# electronicProject.net
KiCad netlist of a schematic drawn in EAGLE
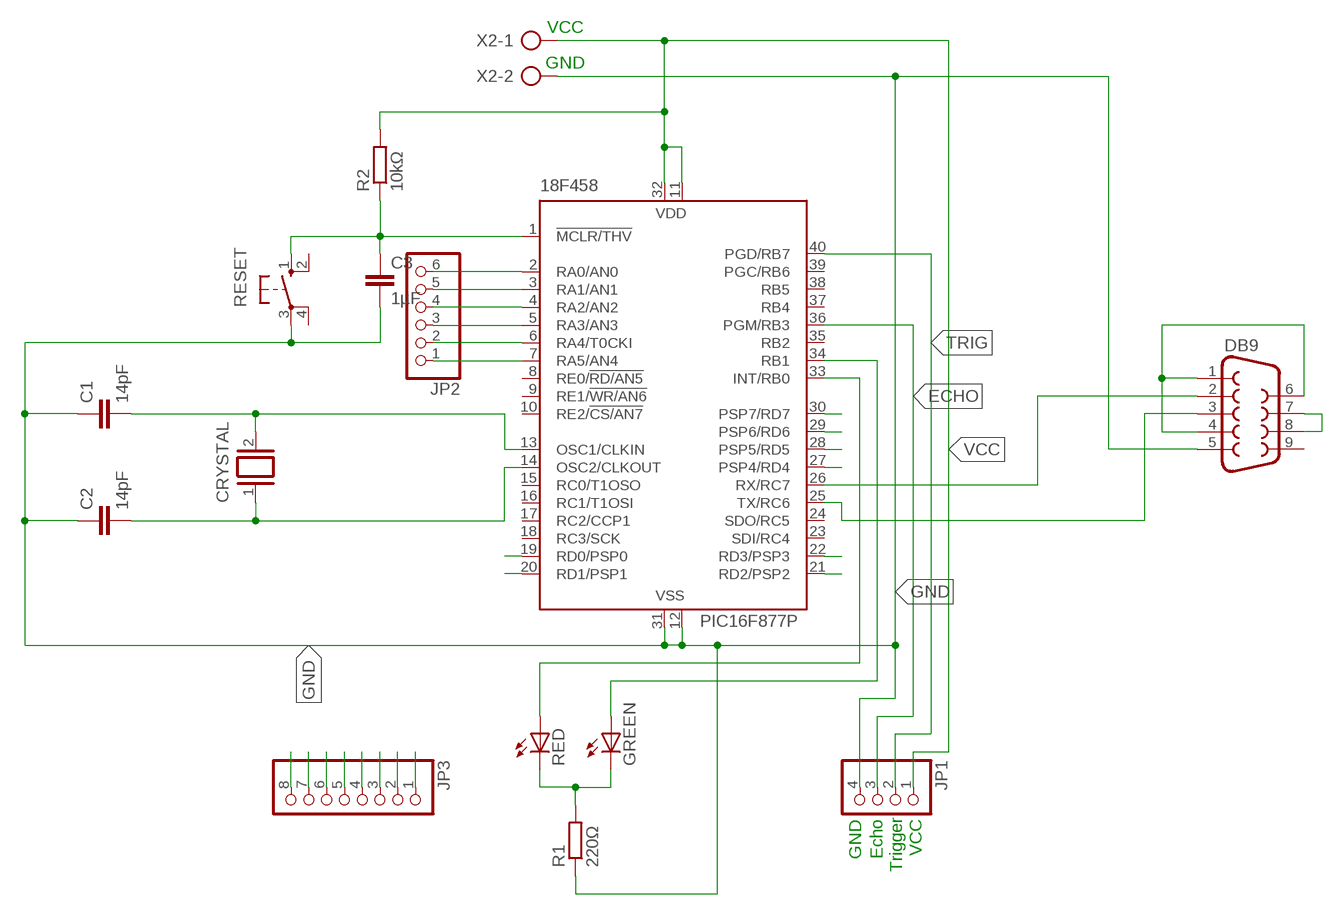
[diagram p0: schematic, sheet 1]

(export (version "E")
  (design (tool "Eeschema 10.0.6"))
  (components
    (comp (ref "18F458")
      (value "PIC16F877P")
      (footprint "eagle-import:DIL40")
      (fields (field (name "MF") "MICROCHIP") (field (name "MPN") "PIC16F877-04/P"))
      (libsource (lib "eagle-import") (part "PIC16F87P7"))
    )
    (comp (ref "C1")
      (value "14pF")
      (footprint "eagle-import:C025-024X044")
      (libsource (lib "eagle-import") (part "C-EU025-024X044"))
    )
    (comp (ref "C2")
      (value "14pF")
      (footprint "eagle-import:C025-024X044")
      (libsource (lib "eagle-import") (part "C-EU025-024X044"))
    )
    (comp (ref "C3")
      (value "1µF")
      (footprint "eagle-import:C025-024X044")
      (libsource (lib "eagle-import") (part "C-EU025-024X044"))
    )
    (comp (ref "CRYSTAL")
      (value "XTAL/S")
      (footprint "eagle-import:QS")
      (libsource (lib "eagle-import") (part "XTAL/S"))
    )
    (comp (ref "DB9")
      (value "F09H")
      (footprint "eagle-import:F09H")
      (libsource (lib "eagle-import") (part "F09H"))
    )
    (comp (ref "GREEN")
      (value "LED3MM")
      (footprint "eagle-import:LED3MM")
      (libsource (lib "eagle-import") (part "LED3MM"))
    )
    (comp (ref "JP1")
      (value "PINHD-1X4")
      (footprint "eagle-import:1X04")
      (libsource (lib "eagle-import") (part "PINHD-1X4"))
    )
    (comp (ref "JP2")
      (value "PINHD-1X6")
      (footprint "eagle-import:1X06")
      (libsource (lib "eagle-import") (part "PINHD-1X6"))
    )
    (comp (ref "JP3")
      (value "PINHD-1X8")
      (footprint "eagle-import:1X08")
      (libsource (lib "eagle-import") (part "PINHD-1X8"))
    )
    (comp (ref "R1")
      (value "220Ω")
      (footprint "eagle-import:0207_10")
      (libsource (lib "eagle-import") (part "R-EU_0207/10"))
    )
    (comp (ref "R2")
      (value "10kΩ")
      (footprint "eagle-import:0207_10")
      (libsource (lib "eagle-import") (part "R-EU_0207/10"))
    )
    (comp (ref "RED")
      (value "LED3MM")
      (footprint "eagle-import:LED3MM")
      (libsource (lib "eagle-import") (part "LED3MM"))
    )
    (comp (ref "RESET")
      (value "10-XX")
      (footprint "eagle-import:B3F-10XX")
      (fields (field (name "MPN") "B3F-1000"))
      (libsource (lib "eagle-import") (part "10-XX"))
    )
    (comp (ref "X2")
      (value "AK300/2")
      (footprint "eagle-import:AK300_2")
      (libsource (lib "eagle-import") (part "AK300/2"))
    )
  )
  (nets
    (net (code "1") (name "/RD0") (class "Default")
      (node (ref "18F458") (pin "19") (pinfunction "RD0/PSP0_19") (pintype "bidirectional"))
      (node (ref "JP3") (pin "8") (pinfunction "8_8") (pintype "passive"))
    )
    (net (code "2") (name "/RD1") (class "Default")
      (node (ref "18F458") (pin "20") (pinfunction "RD1/PSP1_20") (pintype "bidirectional"))
      (node (ref "JP3") (pin "7") (pinfunction "7_7") (pintype "passive"))
    )
    (net (code "3") (name "/RD2") (class "Default")
      (node (ref "18F458") (pin "21") (pinfunction "RD2/PSP2_21") (pintype "bidirectional"))
      (node (ref "JP3") (pin "6") (pinfunction "6_6") (pintype "passive"))
    )
    (net (code "4") (name "/RD3") (class "Default")
      (node (ref "18F458") (pin "22") (pinfunction "RD3/PSP3_22") (pintype "bidirectional"))
      (node (ref "JP3") (pin "5") (pinfunction "5_5") (pintype "passive"))
    )
    (net (code "5") (name "/RD4") (class "Default")
      (node (ref "18F458") (pin "27") (pinfunction "PSP4/RD4_27") (pintype "bidirectional"))
      (node (ref "JP3") (pin "4") (pinfunction "4_4") (pintype "passive"))
    )
    (net (code "6") (name "/RD5") (class "Default")
      (node (ref "18F458") (pin "28") (pinfunction "PSP5/RD5_28") (pintype "bidirectional"))
      (node (ref "JP3") (pin "3") (pinfunction "3_3") (pintype "passive"))
    )
    (net (code "7") (name "/RD6") (class "Default")
      (node (ref "18F458") (pin "29") (pinfunction "PSP6/RD6_29") (pintype "bidirectional"))
      (node (ref "JP3") (pin "2") (pinfunction "2_2") (pintype "passive"))
    )
    (net (code "8") (name "/RD7") (class "Default")
      (node (ref "18F458") (pin "30") (pinfunction "PSP7/RD7_30") (pintype "bidirectional"))
      (node (ref "JP3") (pin "1") (pinfunction "1_1") (pintype "passive"))
    )
    (net (code "9") (name "ECHO") (class "Default")
      (node (ref "18F458") (pin "36") (pinfunction "PGM/RB3_36") (pintype "bidirectional"))
      (node (ref "JP1") (pin "3") (pinfunction "3_3") (pintype "passive"))
    )
    (net (code "10") (name "GND") (class "Default")
      (node (ref "18F458") (pin "12") (pinfunction "VSS_12") (pintype "power_in"))
      (node (ref "18F458") (pin "31") (pinfunction "VSS_31") (pintype "power_in"))
      (node (ref "C1") (pin "1") (pinfunction "1_1") (pintype "passive"))
      (node (ref "C2") (pin "1") (pinfunction "1_1") (pintype "passive"))
      (node (ref "C3") (pin "2") (pinfunction "2_2") (pintype "passive"))
      (node (ref "DB9") (pin "5") (pinfunction "5_5") (pintype "passive"))
      (node (ref "JP1") (pin "4") (pinfunction "4_4") (pintype "passive"))
      (node (ref "R1") (pin "1") (pinfunction "1_1") (pintype "passive"))
      (node (ref "RESET") (pin "3") (pinfunction "P_3") (pintype "passive"))
      (node (ref "X2") (pin "2") (pinfunction "KL_2") (pintype "passive"))
    )
    (net (code "11") (name "Net-(18F458-INT{slash}RB0)") (class "Default")
      (node (ref "18F458") (pin "33") (pinfunction "INT/RB0_33") (pintype "bidirectional"))
      (node (ref "RED") (pin "A") (pinfunction "A_A") (pintype "passive"))
    )
    (net (code "12") (name "Net-(18F458-OSC1{slash}CLKIN)") (class "Default")
      (node (ref "18F458") (pin "13") (pinfunction "OSC1/CLKIN_13") (pintype "input"))
      (node (ref "C1") (pin "2") (pinfunction "2_2") (pintype "passive"))
      (node (ref "CRYSTAL") (pin "2") (pinfunction "2_2") (pintype "passive"))
    )
    (net (code "13") (name "Net-(18F458-OSC2{slash}CLKOUT)") (class "Default")
      (node (ref "18F458") (pin "14") (pinfunction "OSC2/CLKOUT_14") (pintype "output"))
      (node (ref "C2") (pin "2") (pinfunction "2_2") (pintype "passive"))
      (node (ref "CRYSTAL") (pin "1") (pinfunction "1_1") (pintype "passive"))
    )
    (net (code "14") (name "Net-(18F458-RA0{slash}AN0)") (class "Default")
      (node (ref "18F458") (pin "2") (pinfunction "RA0/AN0_2") (pintype "bidirectional"))
      (node (ref "JP2") (pin "6") (pinfunction "6_6") (pintype "passive"))
    )
    (net (code "15") (name "Net-(18F458-RA1{slash}AN1)") (class "Default")
      (node (ref "18F458") (pin "3") (pinfunction "RA1/AN1_3") (pintype "bidirectional"))
      (node (ref "JP2") (pin "5") (pinfunction "5_5") (pintype "passive"))
    )
    (net (code "16") (name "Net-(18F458-RA2{slash}AN2)") (class "Default")
      (node (ref "18F458") (pin "4") (pinfunction "RA2/AN2_4") (pintype "bidirectional"))
      (node (ref "JP2") (pin "4") (pinfunction "4_4") (pintype "passive"))
    )
    (net (code "17") (name "Net-(18F458-RA3{slash}AN3)") (class "Default")
      (node (ref "18F458") (pin "5") (pinfunction "RA3/AN3_5") (pintype "bidirectional"))
      (node (ref "JP2") (pin "3") (pinfunction "3_3") (pintype "passive"))
    )
    (net (code "18") (name "Net-(18F458-RA4{slash}T0CKI)") (class "Default")
      (node (ref "18F458") (pin "6") (pinfunction "RA4/T0CKI_6") (pintype "bidirectional"))
      (node (ref "JP2") (pin "2") (pinfunction "2_2") (pintype "passive"))
    )
    (net (code "19") (name "Net-(18F458-RA5{slash}AN4)") (class "Default")
      (node (ref "18F458") (pin "7") (pinfunction "RA5/AN4_7") (pintype "bidirectional"))
      (node (ref "JP2") (pin "1") (pinfunction "1_1") (pintype "passive"))
    )
    (net (code "20") (name "Net-(18F458-RB1)") (class "Default")
      (node (ref "18F458") (pin "34") (pinfunction "RB1_34") (pintype "bidirectional"))
      (node (ref "GREEN") (pin "A") (pinfunction "A_A") (pintype "passive"))
    )
    (net (code "21") (name "Net-(18F458-RX{slash}RC7)") (class "Default")
      (node (ref "18F458") (pin "26") (pinfunction "RX/RC7_26") (pintype "bidirectional"))
      (node (ref "DB9") (pin "2") (pinfunction "2_2") (pintype "passive"))
    )
    (net (code "22") (name "Net-(18F458-TX{slash}RC6)") (class "Default")
      (node (ref "18F458") (pin "25") (pinfunction "TX/RC6_25") (pintype "bidirectional"))
      (node (ref "DB9") (pin "3") (pinfunction "3_3") (pintype "passive"))
    )
    (net (code "23") (name "Net-(18F458-~{MCLR{slash}THV})") (class "Default")
      (node (ref "18F458") (pin "1") (pinfunction "~{MCLR/THV}_1") (pintype "input"))
      (node (ref "C3") (pin "1") (pinfunction "1_1") (pintype "passive"))
      (node (ref "R2") (pin "1") (pinfunction "1_1") (pintype "passive"))
      (node (ref "RESET") (pin "1") (pinfunction "S_1") (pintype "passive"))
    )
    (net (code "24") (name "Net-(DB9-Pad1)") (class "Default")
      (node (ref "DB9") (pin "1") (pinfunction "1_1") (pintype "passive"))
      (node (ref "DB9") (pin "4") (pinfunction "4_4") (pintype "passive"))
      (node (ref "DB9") (pin "6") (pinfunction "6_6") (pintype "passive"))
    )
    (net (code "25") (name "Net-(DB9-Pad7)") (class "Default")
      (node (ref "DB9") (pin "7") (pinfunction "7_7") (pintype "passive"))
      (node (ref "DB9") (pin "8") (pinfunction "8_8") (pintype "passive"))
    )
    (net (code "26") (name "Net-(GREEN-C)") (class "Default")
      (node (ref "GREEN") (pin "K") (pinfunction "C_K") (pintype "passive"))
      (node (ref "R1") (pin "2") (pinfunction "2_2") (pintype "passive"))
      (node (ref "RED") (pin "K") (pinfunction "C_K") (pintype "passive"))
    )
    (net (code "27") (name "TRIG") (class "Default")
      (node (ref "18F458") (pin "40") (pinfunction "PGD/RB7_40") (pintype "bidirectional"))
      (node (ref "JP1") (pin "2") (pinfunction "2_2") (pintype "passive"))
    )
    (net (code "28") (name "VCC") (class "Default")
      (node (ref "18F458") (pin "11") (pinfunction "VDD_11") (pintype "power_in"))
      (node (ref "18F458") (pin "32") (pinfunction "VDD_32") (pintype "power_in"))
      (node (ref "JP1") (pin "1") (pinfunction "1_1") (pintype "passive"))
      (node (ref "R2") (pin "2") (pinfunction "2_2") (pintype "passive"))
      (node (ref "X2") (pin "1") (pinfunction "KL_1") (pintype "passive"))
    )
    (net (code "29") (name "unconnected-(18F458-PGC{slash}RB6-Pad39)") (class "Default")
      (node (ref "18F458") (pin "39") (pinfunction "PGC/RB6_39") (pintype "bidirectional"))
    )
    (net (code "30") (name "unconnected-(18F458-RB2-Pad35)") (class "Default")
      (node (ref "18F458") (pin "35") (pinfunction "RB2_35") (pintype "bidirectional"))
    )
    (net (code "31") (name "unconnected-(18F458-RB4-Pad37)") (class "Default")
      (node (ref "18F458") (pin "37") (pinfunction "RB4_37") (pintype "bidirectional"))
    )
    (net (code "32") (name "unconnected-(18F458-RB5-Pad38)") (class "Default")
      (node (ref "18F458") (pin "38") (pinfunction "RB5_38") (pintype "bidirectional"))
    )
    (net (code "33") (name "unconnected-(18F458-RC0{slash}T1OSO-Pad15)") (class "Default")
      (node (ref "18F458") (pin "15") (pinfunction "RC0/T1OSO_15") (pintype "bidirectional"))
    )
    (net (code "34") (name "unconnected-(18F458-RC1{slash}T1OSI-Pad16)") (class "Default")
      (node (ref "18F458") (pin "16") (pinfunction "RC1/T1OSI_16") (pintype "bidirectional"))
    )
    (net (code "35") (name "unconnected-(18F458-RC2{slash}CCP1-Pad17)") (class "Default")
      (node (ref "18F458") (pin "17") (pinfunction "RC2/CCP1_17") (pintype "bidirectional"))
    )
    (net (code "36") (name "unconnected-(18F458-RC3{slash}SCK-Pad18)") (class "Default")
      (node (ref "18F458") (pin "18") (pinfunction "RC3/SCK_18") (pintype "bidirectional"))
    )
    (net (code "37") (name "unconnected-(18F458-RE0{slash}~{RD{slash}AN5}-Pad8)") (class "Default")
      (node (ref "18F458") (pin "8") (pinfunction "RE0/~{RD/AN5}_8") (pintype "bidirectional"))
    )
    (net (code "38") (name "unconnected-(18F458-RE1{slash}~{WR{slash}AN6}-Pad9)") (class "Default")
      (node (ref "18F458") (pin "9") (pinfunction "RE1/~{WR/AN6}_9") (pintype "bidirectional"))
    )
    (net (code "39") (name "unconnected-(18F458-RE2{slash}~{CS{slash}AN7}-Pad10)") (class "Default")
      (node (ref "18F458") (pin "10") (pinfunction "RE2/~{CS/AN7}_10") (pintype "bidirectional"))
    )
    (net (code "40") (name "unconnected-(18F458-SDI{slash}RC4-Pad23)") (class "Default")
      (node (ref "18F458") (pin "23") (pinfunction "SDI/RC4_23") (pintype "bidirectional"))
    )
    (net (code "41") (name "unconnected-(18F458-SDO{slash}RC5-Pad24)") (class "Default")
      (node (ref "18F458") (pin "24") (pinfunction "SDO/RC5_24") (pintype "bidirectional"))
    )
    (net (code "42") (name "unconnected-(DB9-Pad9)") (class "Default")
      (node (ref "DB9") (pin "9") (pinfunction "9_9") (pintype "passive"))
    )
    (net (code "43") (name "unconnected-(RESET-P1-Pad4)") (class "Default")
      (node (ref "RESET") (pin "4") (pinfunction "P1_4") (pintype "passive"))
    )
    (net (code "44") (name "unconnected-(RESET-S1-Pad2)") (class "Default")
      (node (ref "RESET") (pin "2") (pinfunction "S1_2") (pintype "passive"))
    )
  )
)
